# NX3215SA-32_768k_Crystall_Oscillator.net
KiCad netlist of a schematic drawn in Altium Designer
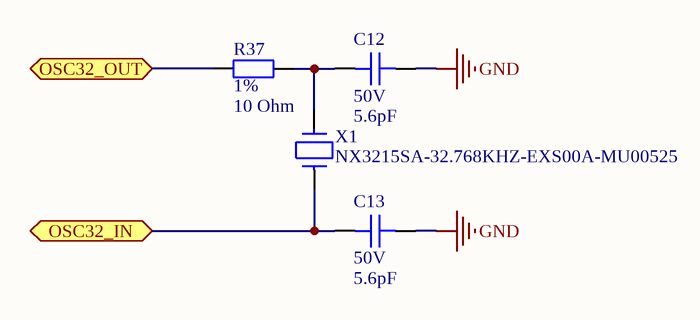
[diagram p0: NX3215SA-32.768k_Crystall_Oscillator.SchDoc]

(export (version "E")
  (design (tool "Eeschema 10.0.6"))
  (components
    (comp (ref "C12")
      (value "CAP CER 5.6PF 50V NPO 0402")
      (footprint "C0402")
      (description "5.6pF ±0.25pF 50V Ceramic Capacitor C0G, NP0 0402 (1005 Metric)")
      (fields
        (field (name "MANUFACTURER") "Yageo")
        (field (name "MANUFACTURER PART NUMBER") "AC0402CRNPO9BN5R6")
        (field (name "VOLTAGE RATING") "50V")
        (field (name "CAPACITANCE") "5.6pF")
      )
      (libsource (lib "capacitors_smd") (part "CAP CER 5.6PF 50V NPO 0402"))
    )
    (comp (ref "C13")
      (value "CAP CER 5.6PF 50V NPO 0402")
      (footprint "C0402")
      (description "5.6pF ±0.25pF 50V Ceramic Capacitor C0G, NP0 0402 (1005 Metric)")
      (fields
        (field (name "MANUFACTURER") "Yageo")
        (field (name "MANUFACTURER PART NUMBER") "AC0402CRNPO9BN5R6")
        (field (name "VOLTAGE RATING") "50V")
        (field (name "CAPACITANCE") "5.6pF")
      )
      (libsource (lib "capacitors_smd") (part "CAP CER 5.6PF 50V NPO 0402"))
    )
    (comp (ref "R37")
      (value "RES SMD 10 OHM 1% 1/16W 0402")
      (footprint "R0402")
      (fields
        (field (name "MANUFACTURER PART NUMBER") "AC0402FR-0710RL")
        (field (name "MANUFACTURER") "Yageo")
        (field (name "TOLERANCE") "1%")
        (field (name "RESISTANCE") "10 Ohm")
      )
      (libsource (lib "resistors_smd") (part "RES SMD 10 OHM 1% 1/16W 0402"))
    )
    (comp (ref "X1")
      (value "NX3215SA-32.768KHZ-EXS00A-MU00525")
      (footprint "XTAL_2SM_3R2X1R5")
      (description "32.768kHz  Crystal 6pF 70 kOhms 2-SMD, No Lead")
      (fields (field (name "MANUFACTURER") "NDK"))
      (libsource (lib "BLDC_Motor_Driver") (part "CRYSTAL 32.768KHZ 6PF SMD"))
    )
  )
  (nets
    (net (code "1") (name "/OSC32_IN") (class "Default")
      (node (ref "C13") (pin "2") (pinfunction "2_2") (pintype "passive"))
      (node (ref "X1") (pin "1") (pinfunction "1_1") (pintype "passive"))
    )
    (net (code "2") (name "/OSC32_OUT") (class "Default")
      (node (ref "R37") (pin "2") (pinfunction "2_2") (pintype "passive"))
    )
    (net (code "3") (name "GND") (class "Default")
      (node (ref "C12") (pin "1") (pinfunction "1_1") (pintype "passive"))
      (node (ref "C13") (pin "1") (pinfunction "1_1") (pintype "passive"))
    )
    (net (code "4") (name "Net-(C12-Pad2)") (class "Default")
      (node (ref "C12") (pin "2") (pinfunction "2_2") (pintype "passive"))
      (node (ref "R37") (pin "1") (pinfunction "1_1") (pintype "passive"))
      (node (ref "X1") (pin "2") (pinfunction "2_2") (pintype "passive"))
    )
  )
)
